# IMU.net
KiCad netlist of a schematic drawn in Altium Designer
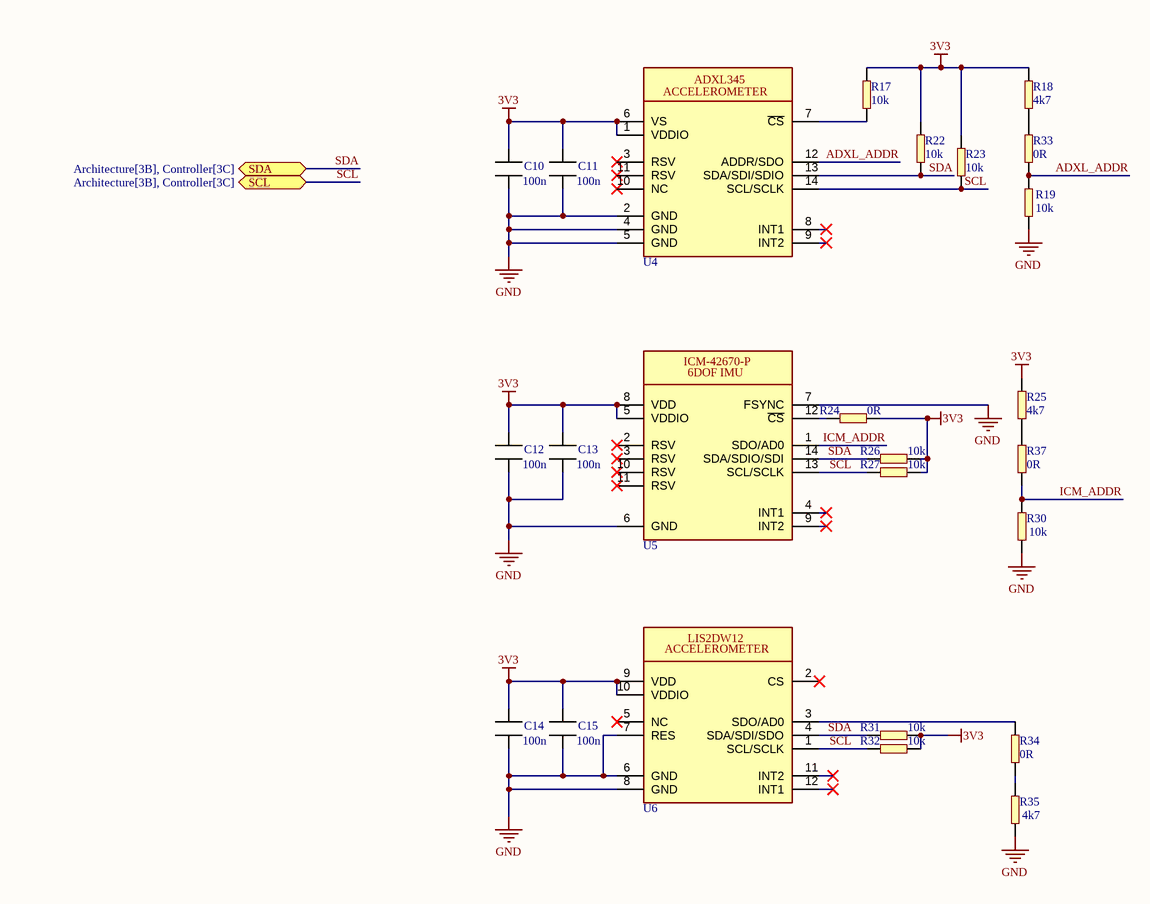
[diagram p0: IMU.SchDoc]

(export (version "E")
  (design (tool "Eeschema 10.0.6"))
  (components
    (comp (ref "C10")
      (value "100n")
      (footprint "CAPC1608X10N")
      (description "Chip Capacitor, 2-Leads, Body 1.60x0.80mm, IPC Medium Density")
      (fields (field (name "Comment") "ERP_102-1"))
      (libsource (lib "Capacitor") (part "MLCC_0603"))
    )
    (comp (ref "C11")
      (value "100n")
      (footprint "CAPC1608X10N")
      (description "Chip Capacitor, 2-Leads, Body 1.60x0.80mm, IPC Medium Density")
      (fields (field (name "Comment") "ERP_102-1"))
      (libsource (lib "Capacitor") (part "MLCC_0603"))
    )
    (comp (ref "C12")
      (value "100n")
      (footprint "CAPC1608X10N")
      (description "Chip Capacitor, 2-Leads, Body 1.60x0.80mm, IPC Medium Density")
      (fields (field (name "Comment") "ERP_102-1"))
      (libsource (lib "Capacitor") (part "MLCC_0603"))
    )
    (comp (ref "C13")
      (value "100n")
      (footprint "CAPC1608X10N")
      (description "Chip Capacitor, 2-Leads, Body 1.60x0.80mm, IPC Medium Density")
      (fields (field (name "Comment") "ERP_102-1"))
      (libsource (lib "Capacitor") (part "MLCC_0603"))
    )
    (comp (ref "C14")
      (value "100n")
      (footprint "CAPC1608X10N")
      (description "Chip Capacitor, 2-Leads, Body 1.60x0.80mm, IPC Medium Density")
      (fields (field (name "Comment") "ERP_102-1"))
      (libsource (lib "Capacitor") (part "MLCC_0603"))
    )
    (comp (ref "C15")
      (value "100n")
      (footprint "CAPC1608X10N")
      (description "Chip Capacitor, 2-Leads, Body 1.60x0.80mm, IPC Medium Density")
      (fields (field (name "Comment") "ERP_102-1"))
      (libsource (lib "Capacitor") (part "MLCC_0603"))
    )
    (comp (ref "R17")
      (value "10k")
      (footprint "RES_0603")
      (description "RES_0603")
      (fields (field (name "Comment") "ERP_101-1"))
      (libsource (lib "Resistor") (part "RES_0603"))
    )
    (comp (ref "R18")
      (value "4k7")
      (footprint "RES_0603")
      (description "RES_0603")
      (fields (field (name "Comment") "ERP_101-1"))
      (libsource (lib "Resistor") (part "RES_0603"))
    )
    (comp (ref "R19")
      (value "10k")
      (footprint "RES_0603")
      (description "RES_0603")
      (fields (field (name "Comment") "ERP_101-1"))
      (libsource (lib "Resistor") (part "RES_0603"))
    )
    (comp (ref "R22")
      (value "10k")
      (footprint "RES_0603")
      (description "RES_0603")
      (fields (field (name "Comment") "ERP_101-1"))
      (libsource (lib "Resistor") (part "RES_0603"))
    )
    (comp (ref "R23")
      (value "10k")
      (footprint "RES_0603")
      (description "RES_0603")
      (fields (field (name "Comment") "ERP_101-1"))
      (libsource (lib "Resistor") (part "RES_0603"))
    )
    (comp (ref "R24")
      (value "0R")
      (footprint "RES_0603")
      (description "RES_0603")
      (fields (field (name "Comment") "ERP_101-1"))
      (libsource (lib "") (part "RES_0603_1"))
    )
    (comp (ref "R25")
      (value "4k7")
      (footprint "RES_0603")
      (description "RES_0603")
      (fields (field (name "Comment") "ERP_101-1"))
      (libsource (lib "Resistor") (part "RES_0603"))
    )
    (comp (ref "R26")
      (value "10k")
      (footprint "RES_0603")
      (description "RES_0603")
      (fields (field (name "Comment") "ERP_101-1"))
      (libsource (lib "") (part "RES_0603_1"))
    )
    (comp (ref "R27")
      (value "10k")
      (footprint "RES_0603")
      (description "RES_0603")
      (fields (field (name "Comment") "ERP_101-1"))
      (libsource (lib "") (part "RES_0603_1"))
    )
    (comp (ref "R30")
      (value "10k")
      (footprint "RES_0603")
      (description "RES_0603")
      (fields (field (name "Comment") "ERP_101-1"))
      (libsource (lib "Resistor") (part "RES_0603"))
    )
    (comp (ref "R31")
      (value "10k")
      (footprint "RES_0603")
      (description "RES_0603")
      (fields (field (name "Comment") "ERP_101-1"))
      (libsource (lib "") (part "RES_0603_1"))
    )
    (comp (ref "R32")
      (value "10k")
      (footprint "RES_0603")
      (description "RES_0603")
      (fields (field (name "Comment") "ERP_101-1"))
      (libsource (lib "") (part "RES_0603_1"))
    )
    (comp (ref "R33")
      (value "0R")
      (footprint "RES_0603")
      (description "RES_0603")
      (fields (field (name "Comment") "ERP_101-1"))
      (libsource (lib "Resistor") (part "RES_0603"))
    )
    (comp (ref "R34")
      (value "0R")
      (footprint "RES_0603")
      (description "RES_0603")
      (fields (field (name "Comment") "ERP_101-1"))
      (libsource (lib "Resistor") (part "RES_0603"))
    )
    (comp (ref "R35")
      (value "4k7")
      (footprint "RES_0603")
      (description "RES_0603")
      (fields (field (name "Comment") "ERP_101-1"))
      (libsource (lib "Resistor") (part "RES_0603"))
    )
    (comp (ref "R37")
      (value "0R")
      (footprint "RES_0603")
      (description "RES_0603")
      (fields (field (name "Comment") "ERP_101-1"))
      (libsource (lib "Resistor") (part "RES_0603"))
    )
    (comp (ref "U4")
      (value "ADXL345")
      (footprint "ADXL345")
      (description "ACCEL 2-16G I2C/SPI 14LGA")
      (libsource (lib "IMU") (part "ADXL345"))
    )
    (comp (ref "U5")
      (value "ICM42670P")
      (footprint "ICM42670P")
      (description "IMU ACCEL/GYRO/TEMP I2C/SPI")
      (libsource (lib "IMU") (part "ICM42670P"))
    )
    (comp (ref "U6")
      (value "LIS2DW12")
      (footprint "LIS2DW12")
      (description "ACCEL 2-16G I2C/SPI 12LGA")
      (libsource (lib "IMU") (part "LIS2DW12"))
    )
  )
  (nets
    (net (code "1") (name "/ADXL_ADDR") (class "Default")
      (node (ref "R19") (pin "2") (pinfunction "2_2") (pintype "passive"))
      (node (ref "R33") (pin "1") (pinfunction "1_1") (pintype "passive"))
      (node (ref "U4") (pin "12") (pinfunction "ADDR/SDO_12") (pintype "passive"))
    )
    (net (code "2") (name "/ICM_ADDR") (class "Default")
      (node (ref "R30") (pin "2") (pinfunction "2_2") (pintype "passive"))
      (node (ref "R37") (pin "1") (pinfunction "1_1") (pintype "passive"))
      (node (ref "U5") (pin "1") (pinfunction "SDO/AD0_1") (pintype "passive"))
    )
    (net (code "3") (name "/SCL") (class "Default")
      (node (ref "R23") (pin "1") (pinfunction "1_1") (pintype "passive"))
      (node (ref "R27") (pin "2") (pinfunction "2_2") (pintype "passive"))
      (node (ref "R32") (pin "2") (pinfunction "2_2") (pintype "passive"))
      (node (ref "U4") (pin "14") (pinfunction "SCL/SCLK_14") (pintype "passive"))
      (node (ref "U5") (pin "13") (pinfunction "SCL/SCLK_13") (pintype "passive"))
      (node (ref "U6") (pin "1") (pinfunction "SCL/SCLK_1") (pintype "passive"))
    )
    (net (code "4") (name "/SDA") (class "Default")
      (node (ref "R22") (pin "1") (pinfunction "1_1") (pintype "passive"))
      (node (ref "R26") (pin "2") (pinfunction "2_2") (pintype "passive"))
      (node (ref "R31") (pin "2") (pinfunction "2_2") (pintype "passive"))
      (node (ref "U4") (pin "13") (pinfunction "SDA/SDI/SDIO_13") (pintype "passive"))
      (node (ref "U5") (pin "14") (pinfunction "SDA/SDIO/SDI_14") (pintype "passive"))
      (node (ref "U6") (pin "4") (pinfunction "SDA/SDI/SDO_4") (pintype "passive"))
    )
    (net (code "5") (name "3V3") (class "Default")
      (node (ref "C10") (pin "1") (pinfunction "1_1") (pintype "passive"))
      (node (ref "C11") (pin "1") (pinfunction "1_1") (pintype "passive"))
      (node (ref "C12") (pin "1") (pinfunction "1_1") (pintype "passive"))
      (node (ref "C13") (pin "1") (pinfunction "1_1") (pintype "passive"))
      (node (ref "C14") (pin "1") (pinfunction "1_1") (pintype "passive"))
      (node (ref "C15") (pin "1") (pinfunction "1_1") (pintype "passive"))
      (node (ref "R17") (pin "2") (pinfunction "2_2") (pintype "passive"))
      (node (ref "R18") (pin "2") (pinfunction "2_2") (pintype "passive"))
      (node (ref "R22") (pin "2") (pinfunction "2_2") (pintype "passive"))
      (node (ref "R23") (pin "2") (pinfunction "2_2") (pintype "passive"))
      (node (ref "R24") (pin "1") (pinfunction "1_1") (pintype "passive"))
      (node (ref "R25") (pin "2") (pinfunction "2_2") (pintype "passive"))
      (node (ref "R26") (pin "1") (pinfunction "1_1") (pintype "passive"))
      (node (ref "R27") (pin "1") (pinfunction "1_1") (pintype "passive"))
      (node (ref "R31") (pin "1") (pinfunction "1_1") (pintype "passive"))
      (node (ref "R32") (pin "1") (pinfunction "1_1") (pintype "passive"))
      (node (ref "U4") (pin "1") (pinfunction "VDDIO_1") (pintype "passive"))
      (node (ref "U4") (pin "6") (pinfunction "VS_6") (pintype "passive"))
      (node (ref "U5") (pin "5") (pinfunction "VDDIO_5") (pintype "passive"))
      (node (ref "U5") (pin "8") (pinfunction "VDD_8") (pintype "passive"))
      (node (ref "U6") (pin "10") (pinfunction "VDDIO_10") (pintype "passive"))
      (node (ref "U6") (pin "9") (pinfunction "VDD_9") (pintype "passive"))
    )
    (net (code "6") (name "GND") (class "Default")
      (node (ref "C10") (pin "2") (pinfunction "2_2") (pintype "passive"))
      (node (ref "C11") (pin "2") (pinfunction "2_2") (pintype "passive"))
      (node (ref "C12") (pin "2") (pinfunction "2_2") (pintype "passive"))
      (node (ref "C13") (pin "2") (pinfunction "2_2") (pintype "passive"))
      (node (ref "C14") (pin "2") (pinfunction "2_2") (pintype "passive"))
      (node (ref "C15") (pin "2") (pinfunction "2_2") (pintype "passive"))
      (node (ref "R19") (pin "1") (pinfunction "1_1") (pintype "passive"))
      (node (ref "R30") (pin "1") (pinfunction "1_1") (pintype "passive"))
      (node (ref "R35") (pin "1") (pinfunction "1_1") (pintype "passive"))
      (node (ref "U4") (pin "2") (pinfunction "GND_2") (pintype "passive"))
      (node (ref "U4") (pin "4") (pinfunction "GND_4") (pintype "passive"))
      (node (ref "U4") (pin "5") (pinfunction "GND_5") (pintype "passive"))
      (node (ref "U5") (pin "6") (pinfunction "GND_6") (pintype "passive"))
      (node (ref "U5") (pin "7") (pinfunction "FSYNC_7") (pintype "passive"))
      (node (ref "U6") (pin "6") (pinfunction "GND_6") (pintype "passive"))
      (node (ref "U6") (pin "7") (pinfunction "RES_7") (pintype "passive"))
      (node (ref "U6") (pin "8") (pinfunction "GND_8") (pintype "passive"))
    )
    (net (code "7") (name "Net-(R18-Pad1)") (class "Default")
      (node (ref "R18") (pin "1") (pinfunction "1_1") (pintype "passive"))
      (node (ref "R33") (pin "2") (pinfunction "2_2") (pintype "passive"))
    )
    (net (code "8") (name "Net-(R25-Pad1)") (class "Default")
      (node (ref "R25") (pin "1") (pinfunction "1_1") (pintype "passive"))
      (node (ref "R37") (pin "2") (pinfunction "2_2") (pintype "passive"))
    )
    (net (code "9") (name "Net-(R34-Pad1)") (class "Default")
      (node (ref "R34") (pin "1") (pinfunction "1_1") (pintype "passive"))
      (node (ref "R35") (pin "2") (pinfunction "2_2") (pintype "passive"))
    )
    (net (code "10") (name "Net-(U4-~{CS})") (class "Default")
      (node (ref "R17") (pin "1") (pinfunction "1_1") (pintype "passive"))
      (node (ref "U4") (pin "7") (pinfunction "~{CS}_7") (pintype "passive"))
    )
    (net (code "11") (name "Net-(U5-~{CS})") (class "Default")
      (node (ref "R24") (pin "2") (pinfunction "2_2") (pintype "passive"))
      (node (ref "U5") (pin "12") (pinfunction "~{CS}_12") (pintype "passive"))
    )
    (net (code "12") (name "Net-(U6-SDO{slash}AD0)") (class "Default")
      (node (ref "R34") (pin "2") (pinfunction "2_2") (pintype "passive"))
      (node (ref "U6") (pin "3") (pinfunction "SDO/AD0_3") (pintype "passive"))
    )
    (net (code "13") (name "unconnected-(U4-INT1-Pad8)") (class "Default")
      (node (ref "U4") (pin "8") (pinfunction "INT1_8") (pintype "passive+no_connect"))
    )
    (net (code "14") (name "unconnected-(U4-INT2-Pad9)") (class "Default")
      (node (ref "U4") (pin "9") (pinfunction "INT2_9") (pintype "passive+no_connect"))
    )
    (net (code "15") (name "unconnected-(U4-NC-Pad10)") (class "Default")
      (node (ref "U4") (pin "10") (pinfunction "NC_10") (pintype "passive+no_connect"))
    )
    (net (code "16") (name "unconnected-(U4-RSV-Pad3)") (class "Default")
      (node (ref "U4") (pin "3") (pinfunction "RSV_3") (pintype "passive+no_connect"))
    )
    (net (code "17") (name "unconnected-(U4-RSV-Pad11)") (class "Default")
      (node (ref "U4") (pin "11") (pinfunction "RSV_11") (pintype "passive+no_connect"))
    )
    (net (code "18") (name "unconnected-(U5-INT1-Pad4)") (class "Default")
      (node (ref "U5") (pin "4") (pinfunction "INT1_4") (pintype "passive+no_connect"))
    )
    (net (code "19") (name "unconnected-(U5-INT2-Pad9)") (class "Default")
      (node (ref "U5") (pin "9") (pinfunction "INT2_9") (pintype "passive+no_connect"))
    )
    (net (code "20") (name "unconnected-(U5-RSV-Pad2)") (class "Default")
      (node (ref "U5") (pin "2") (pinfunction "RSV_2") (pintype "passive+no_connect"))
    )
    (net (code "21") (name "unconnected-(U5-RSV-Pad3)") (class "Default")
      (node (ref "U5") (pin "3") (pinfunction "RSV_3") (pintype "passive+no_connect"))
    )
    (net (code "22") (name "unconnected-(U5-RSV-Pad10)") (class "Default")
      (node (ref "U5") (pin "10") (pinfunction "RSV_10") (pintype "passive+no_connect"))
    )
    (net (code "23") (name "unconnected-(U5-RSV-Pad11)") (class "Default")
      (node (ref "U5") (pin "11") (pinfunction "RSV_11") (pintype "passive+no_connect"))
    )
    (net (code "24") (name "unconnected-(U6-CS-Pad2)") (class "Default")
      (node (ref "U6") (pin "2") (pinfunction "CS_2") (pintype "passive+no_connect"))
    )
    (net (code "25") (name "unconnected-(U6-INT1-Pad12)") (class "Default")
      (node (ref "U6") (pin "12") (pinfunction "INT1_12") (pintype "passive+no_connect"))
    )
    (net (code "26") (name "unconnected-(U6-INT2-Pad11)") (class "Default")
      (node (ref "U6") (pin "11") (pinfunction "INT2_11") (pintype "passive+no_connect"))
    )
    (net (code "27") (name "unconnected-(U6-NC-Pad5)") (class "Default")
      (node (ref "U6") (pin "5") (pinfunction "NC_5") (pintype "passive+no_connect"))
    )
  )
)
